# 05_POWER-SUPPLY.net
KiCad netlist of a schematic drawn in Altium Designer
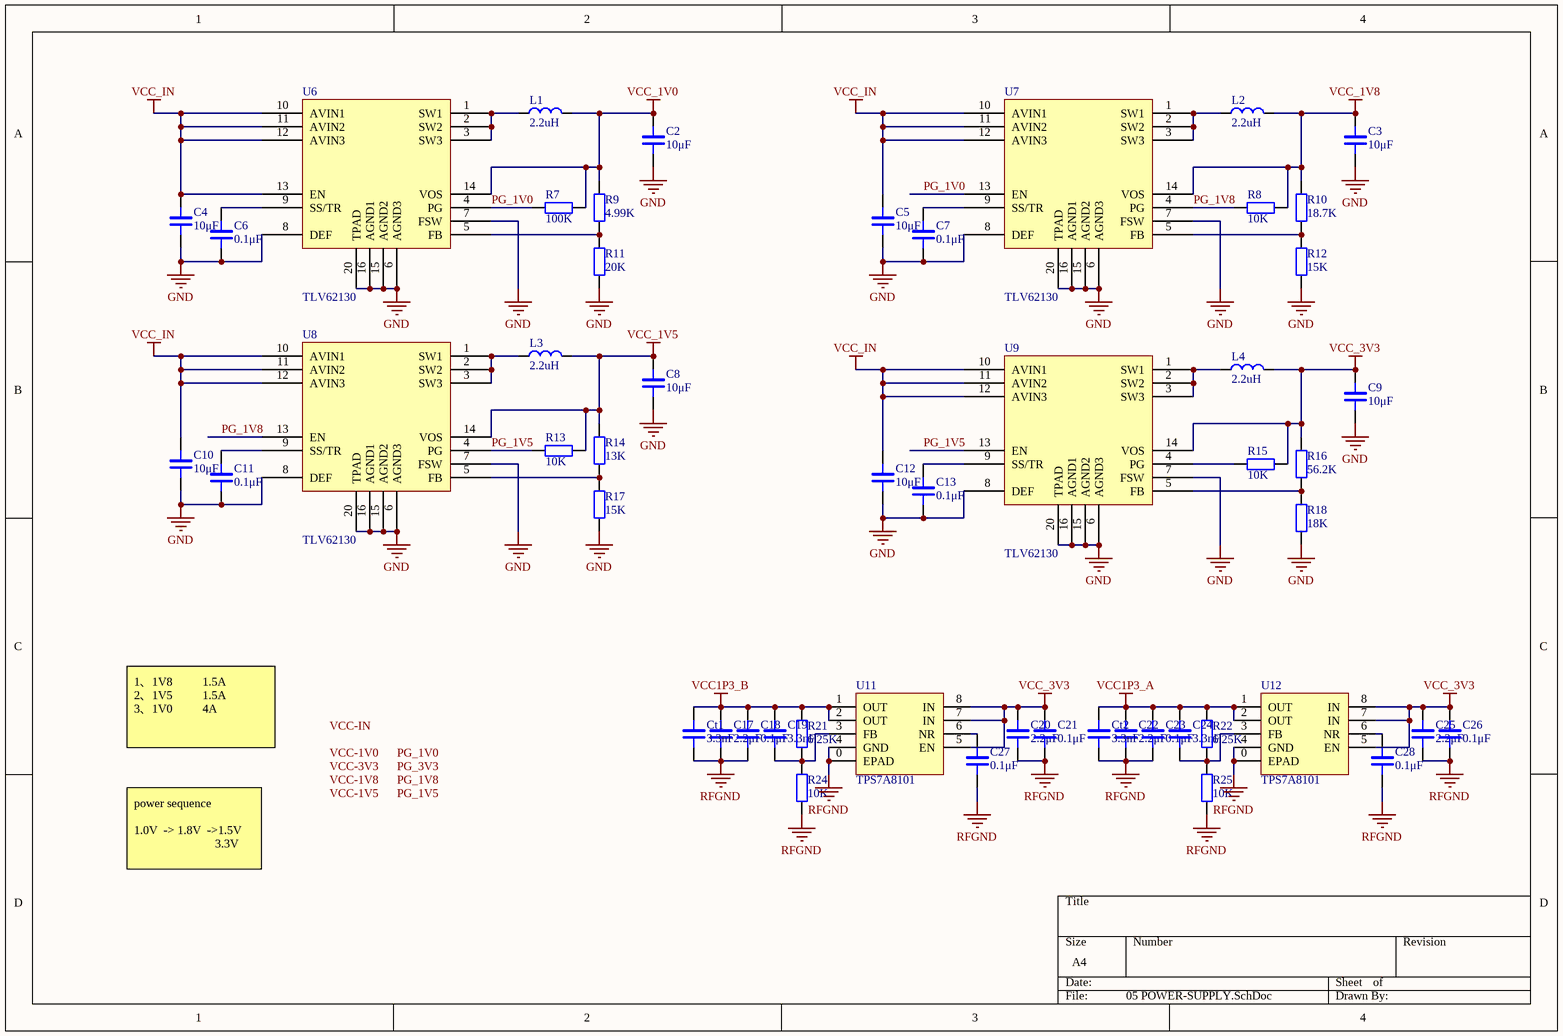
[diagram p0: 05 POWER-SUPPLY.SchDoc]

(export (version "E")
  (design (tool "Eeschema 10.0.6"))
  (components
    (comp (ref "C2")
      (value "10μF")
      (footprint "LC-0805_C")
      (description "Capacitor")
      (libsource (lib "NGFF_M_Key_xc7z010-clg400") (part "CAP_3"))
    )
    (comp (ref "C3")
      (value "10μF")
      (footprint "LC-0805_C")
      (description "Capacitor")
      (libsource (lib "NGFF_M_Key_xc7z010-clg400") (part "CAP_3"))
    )
    (comp (ref "C4")
      (value "10μF")
      (footprint "LC-0805_C")
      (description "Capacitor")
      (libsource (lib "NGFF_M_Key_xc7z010-clg400") (part "CAP_3"))
    )
    (comp (ref "C5")
      (value "10μF")
      (footprint "LC-0805_C")
      (description "Capacitor")
      (libsource (lib "NGFF_M_Key_xc7z010-clg400") (part "CAP_3"))
    )
    (comp (ref "C6")
      (value "0.1μF")
      (footprint "LC-0402_C")
      (description "Capacitor")
      (libsource (lib "NGFF_M_Key_xc7z010-clg400") (part "CAP_3"))
    )
    (comp (ref "C7")
      (value "0.1μF")
      (footprint "LC-0402_C")
      (description "Capacitor")
      (libsource (lib "NGFF_M_Key_xc7z010-clg400") (part "CAP_3"))
    )
    (comp (ref "C8")
      (value "10μF")
      (footprint "LC-0805_C")
      (description "Capacitor")
      (libsource (lib "NGFF_M_Key_xc7z010-clg400") (part "CAP_3"))
    )
    (comp (ref "C9")
      (value "10μF")
      (footprint "LC-0805_C")
      (description "Capacitor")
      (libsource (lib "NGFF_M_Key_xc7z010-clg400") (part "CAP_3"))
    )
    (comp (ref "C10")
      (value "10μF")
      (footprint "LC-0805_C")
      (description "Capacitor")
      (libsource (lib "NGFF_M_Key_xc7z010-clg400") (part "CAP_3"))
    )
    (comp (ref "C11")
      (value "0.1μF")
      (footprint "LC-0402_C")
      (description "Capacitor")
      (libsource (lib "NGFF_M_Key_xc7z010-clg400") (part "CAP_3"))
    )
    (comp (ref "C12")
      (value "10μF")
      (footprint "LC-0805_C")
      (description "Capacitor")
      (libsource (lib "NGFF_M_Key_xc7z010-clg400") (part "CAP_3"))
    )
    (comp (ref "C13")
      (value "0.1μF")
      (footprint "LC-0402_C")
      (description "Capacitor")
      (libsource (lib "NGFF_M_Key_xc7z010-clg400") (part "CAP_3"))
    )
    (comp (ref "C17")
      (value "2.2μF")
      (footprint "LC-0805_C")
      (description "Capacitor")
      (libsource (lib "NGFF_M_Key_xc7z010-clg400") (part "CAP_3"))
    )
    (comp (ref "C18")
      (value "0.1μF")
      (footprint "LC-0402_C")
      (description "Capacitor")
      (libsource (lib "NGFF_M_Key_xc7z010-clg400") (part "CAP_3"))
    )
    (comp (ref "C19")
      (value "3.3nF")
      (footprint "LC-0402_C")
      (description "Capacitor")
      (libsource (lib "NGFF_M_Key_xc7z010-clg400") (part "CAP_3"))
    )
    (comp (ref "C20")
      (value "2.2μF")
      (footprint "LC-0402_C")
      (description "Capacitor")
      (libsource (lib "NGFF_M_Key_xc7z010-clg400") (part "CAP_3"))
    )
    (comp (ref "C21")
      (value "0.1μF")
      (footprint "LC-0805_C")
      (description "Capacitor")
      (libsource (lib "NGFF_M_Key_xc7z010-clg400") (part "CAP_3"))
    )
    (comp (ref "C22")
      (value "2.2μF")
      (footprint "LC-0805_C")
      (description "Capacitor")
      (libsource (lib "NGFF_M_Key_xc7z010-clg400") (part "CAP_3"))
    )
    (comp (ref "C23")
      (value "0.1μF")
      (footprint "LC-0402_C")
      (description "Capacitor")
      (libsource (lib "NGFF_M_Key_xc7z010-clg400") (part "CAP_3"))
    )
    (comp (ref "C24")
      (value "3.3nF")
      (footprint "LC-0402_C")
      (description "Capacitor")
      (libsource (lib "NGFF_M_Key_xc7z010-clg400") (part "CAP_3"))
    )
    (comp (ref "C25")
      (value "2.2μF")
      (footprint "LC-0402_C")
      (description "Capacitor")
      (libsource (lib "NGFF_M_Key_xc7z010-clg400") (part "CAP_3"))
    )
    (comp (ref "C26")
      (value "0.1μF")
      (footprint "LC-0805_C")
      (description "Capacitor")
      (libsource (lib "NGFF_M_Key_xc7z010-clg400") (part "CAP_3"))
    )
    (comp (ref "C27")
      (value "0.1μF")
      (footprint "LC-0402_C")
      (description "Capacitor")
      (libsource (lib "NGFF_M_Key_xc7z010-clg400") (part "CAP_3"))
    )
    (comp (ref "C28")
      (value "0.1μF")
      (footprint "LC-0402_C")
      (description "Capacitor")
      (libsource (lib "NGFF_M_Key_xc7z010-clg400") (part "CAP_3"))
    )
    (comp (ref "Ct1")
      (value "3.3nF")
      (footprint "PCBComponent_1")
      (description "Capacitor")
      (libsource (lib "ZYNQ7010_AD9363") (part "CAP_3_3"))
    )
    (comp (ref "Ct2")
      (value "3.3nF")
      (footprint "PCBComponent_1")
      (description "Capacitor")
      (libsource (lib "ZYNQ7010_AD9363") (part "CAP_3_3"))
    )
    (comp (ref "L1")
      (value "2.2uH")
      (footprint "L1008")
      (description "Inductance")
      (libsource (lib "NGFF_M_Key_xc7z010-clg400") (part "INDUCTANCE_1"))
    )
    (comp (ref "L2")
      (value "2.2uH")
      (footprint "L1008")
      (description "Inductance")
      (libsource (lib "NGFF_M_Key_xc7z010-clg400") (part "INDUCTANCE_1"))
    )
    (comp (ref "L3")
      (value "2.2uH")
      (footprint "L1008")
      (description "Inductance")
      (libsource (lib "NGFF_M_Key_xc7z010-clg400") (part "INDUCTANCE_1"))
    )
    (comp (ref "L4")
      (value "2.2uH")
      (footprint "L1008")
      (description "Inductance")
      (libsource (lib "NGFF_M_Key_xc7z010-clg400") (part "INDUCTANCE_1"))
    )
    (comp (ref "R7")
      (value "100K")
      (footprint "LC-0402_R")
      (description "Resistor")
      (libsource (lib "") (part "RES_1"))
    )
    (comp (ref "R8")
      (value "10K")
      (footprint "LC-0402_R")
      (description "Resistor")
      (libsource (lib "") (part "RES_1"))
    )
    (comp (ref "R9")
      (value "4.99K")
      (footprint "LC-0402_R")
      (description "Resistor")
      (libsource (lib "NGFF_M_Key_xc7z010-clg400") (part "RES"))
    )
    (comp (ref "R10")
      (value "18.7K")
      (footprint "LC-0402_R")
      (description "Resistor")
      (libsource (lib "NGFF_M_Key_xc7z010-clg400") (part "RES"))
    )
    (comp (ref "R11")
      (value "20K")
      (footprint "LC-0402_R")
      (description "Resistor")
      (libsource (lib "NGFF_M_Key_xc7z010-clg400") (part "RES"))
    )
    (comp (ref "R12")
      (value "15K")
      (footprint "LC-0402_R")
      (description "Resistor")
      (libsource (lib "NGFF_M_Key_xc7z010-clg400") (part "RES"))
    )
    (comp (ref "R13")
      (value "10K")
      (footprint "LC-0402_R")
      (description "Resistor")
      (libsource (lib "") (part "RES_1"))
    )
    (comp (ref "R14")
      (value "13K")
      (footprint "LC-0402_R")
      (description "Resistor")
      (libsource (lib "NGFF_M_Key_xc7z010-clg400") (part "RES"))
    )
    (comp (ref "R15")
      (value "10K")
      (footprint "LC-0402_R")
      (description "Resistor")
      (libsource (lib "") (part "RES_1"))
    )
    (comp (ref "R16")
      (value "56.2K")
      (footprint "LC-0402_R")
      (description "Resistor")
      (libsource (lib "NGFF_M_Key_xc7z010-clg400") (part "RES"))
    )
    (comp (ref "R17")
      (value "15K")
      (footprint "LC-0402_R")
      (description "Resistor")
      (libsource (lib "NGFF_M_Key_xc7z010-clg400") (part "RES"))
    )
    (comp (ref "R18")
      (value "18K")
      (footprint "LC-0402_R")
      (description "Resistor")
      (libsource (lib "NGFF_M_Key_xc7z010-clg400") (part "RES"))
    )
    (comp (ref "R21")
      (value "6.25K")
      (footprint "LC-0402_R")
      (description "Resistor")
      (libsource (lib "NGFF_M_Key_xc7z010-clg400") (part "RES"))
    )
    (comp (ref "R22")
      (value "6.25K")
      (footprint "LC-0402_R")
      (description "Resistor")
      (libsource (lib "NGFF_M_Key_xc7z010-clg400") (part "RES"))
    )
    (comp (ref "R24")
      (value "10K")
      (footprint "LC-0402_R")
      (description "Resistor")
      (libsource (lib "NGFF_M_Key_xc7z010-clg400") (part "RES"))
    )
    (comp (ref "R25")
      (value "10K")
      (footprint "LC-0402_R")
      (description "Resistor")
      (libsource (lib "NGFF_M_Key_xc7z010-clg400") (part "RES"))
    )
    (comp (ref "U6")
      (value "TLV62130")
      (footprint "TLV62130RGT")
      (libsource (lib "PCB_Project") (part "TLV62130"))
    )
    (comp (ref "U7")
      (value "TLV62130")
      (footprint "TLV62130RGT")
      (libsource (lib "PCB_Project") (part "TLV62130"))
    )
    (comp (ref "U8")
      (value "TLV62130")
      (footprint "TLV62130RGT")
      (libsource (lib "PCB_Project") (part "TLV62130"))
    )
    (comp (ref "U9")
      (value "TLV62130")
      (footprint "TLV62130RGT")
      (libsource (lib "PCB_Project") (part "TLV62130"))
    )
    (comp (ref "U11")
      (value "TPS7A8101")
      (footprint "TPS7A8101")
      (libsource (lib "AD9363_ZYNQ_V2") (part "TPS7A8101"))
    )
    (comp (ref "U12")
      (value "TPS7A8101")
      (footprint "TPS7A8101")
      (libsource (lib "AD9363_ZYNQ_V2") (part "TPS7A8101"))
    )
  )
  (nets
    (net (code "1") (name "/PG_1V0") (class "Default")
      (node (ref "R7") (pin "2") (pinfunction "2_2") (pintype "passive"))
      (node (ref "U6") (pin "4") (pinfunction "PG_4") (pintype "passive"))
      (node (ref "U7") (pin "13") (pinfunction "EN_13") (pintype "passive"))
    )
    (net (code "2") (name "/PG_1V5") (class "Default")
      (node (ref "R13") (pin "2") (pinfunction "2_2") (pintype "passive"))
      (node (ref "U8") (pin "4") (pinfunction "PG_4") (pintype "passive"))
      (node (ref "U9") (pin "13") (pinfunction "EN_13") (pintype "passive"))
    )
    (net (code "3") (name "/PG_1V8") (class "Default")
      (node (ref "R8") (pin "2") (pinfunction "2_2") (pintype "passive"))
      (node (ref "U7") (pin "4") (pinfunction "PG_4") (pintype "passive"))
      (node (ref "U8") (pin "13") (pinfunction "EN_13") (pintype "passive"))
    )
    (net (code "10") (name "GND") (class "Default")
      (node (ref "C10") (pin "1") (pinfunction "1_1") (pintype "passive"))
      (node (ref "C11") (pin "1") (pinfunction "1_1") (pintype "passive"))
      (node (ref "C12") (pin "1") (pinfunction "1_1") (pintype "passive"))
      (node (ref "C13") (pin "1") (pinfunction "1_1") (pintype "passive"))
      (node (ref "C2") (pin "1") (pinfunction "1_1") (pintype "passive"))
      (node (ref "C3") (pin "1") (pinfunction "1_1") (pintype "passive"))
      (node (ref "C4") (pin "1") (pinfunction "1_1") (pintype "passive"))
      (node (ref "C5") (pin "1") (pinfunction "1_1") (pintype "passive"))
      (node (ref "C6") (pin "1") (pinfunction "1_1") (pintype "passive"))
      (node (ref "C7") (pin "1") (pinfunction "1_1") (pintype "passive"))
      (node (ref "C8") (pin "1") (pinfunction "1_1") (pintype "passive"))
      (node (ref "C9") (pin "1") (pinfunction "1_1") (pintype "passive"))
      (node (ref "R11") (pin "2") (pinfunction "2_2") (pintype "passive"))
      (node (ref "R12") (pin "2") (pinfunction "2_2") (pintype "passive"))
      (node (ref "R17") (pin "2") (pinfunction "2_2") (pintype "passive"))
      (node (ref "R18") (pin "2") (pinfunction "2_2") (pintype "passive"))
      (node (ref "U6") (pin "15") (pinfunction "AGND2_15") (pintype "passive"))
      (node (ref "U6") (pin "16") (pinfunction "AGND1_16") (pintype "passive"))
      (node (ref "U6") (pin "20") (pinfunction "TPAD_20") (pintype "passive"))
      (node (ref "U6") (pin "6") (pinfunction "AGND3_6") (pintype "passive"))
      (node (ref "U6") (pin "7") (pinfunction "FSW_7") (pintype "passive"))
      (node (ref "U6") (pin "8") (pinfunction "DEF_8") (pintype "passive"))
      (node (ref "U7") (pin "15") (pinfunction "AGND2_15") (pintype "passive"))
      (node (ref "U7") (pin "16") (pinfunction "AGND1_16") (pintype "passive"))
      (node (ref "U7") (pin "20") (pinfunction "TPAD_20") (pintype "passive"))
      (node (ref "U7") (pin "6") (pinfunction "AGND3_6") (pintype "passive"))
      (node (ref "U7") (pin "7") (pinfunction "FSW_7") (pintype "passive"))
      (node (ref "U7") (pin "8") (pinfunction "DEF_8") (pintype "passive"))
      (node (ref "U8") (pin "15") (pinfunction "AGND2_15") (pintype "passive"))
      (node (ref "U8") (pin "16") (pinfunction "AGND1_16") (pintype "passive"))
      (node (ref "U8") (pin "20") (pinfunction "TPAD_20") (pintype "passive"))
      (node (ref "U8") (pin "6") (pinfunction "AGND3_6") (pintype "passive"))
      (node (ref "U8") (pin "7") (pinfunction "FSW_7") (pintype "passive"))
      (node (ref "U8") (pin "8") (pinfunction "DEF_8") (pintype "passive"))
      (node (ref "U9") (pin "15") (pinfunction "AGND2_15") (pintype "passive"))
      (node (ref "U9") (pin "16") (pinfunction "AGND1_16") (pintype "passive"))
      (node (ref "U9") (pin "20") (pinfunction "TPAD_20") (pintype "passive"))
      (node (ref "U9") (pin "6") (pinfunction "AGND3_6") (pintype "passive"))
      (node (ref "U9") (pin "7") (pinfunction "FSW_7") (pintype "passive"))
      (node (ref "U9") (pin "8") (pinfunction "DEF_8") (pintype "passive"))
    )
    (net (code "11") (name "Net-(U6-FB)") (class "Default")
      (node (ref "R11") (pin "1") (pinfunction "1_1") (pintype "passive"))
      (node (ref "R9") (pin "2") (pinfunction "2_2") (pintype "passive"))
      (node (ref "U6") (pin "5") (pinfunction "FB_5") (pintype "passive"))
    )
    (net (code "12") (name "Net-(U6-SS{slash}TR)") (class "Default")
      (node (ref "C6") (pin "2") (pinfunction "2_2") (pintype "passive"))
      (node (ref "U6") (pin "9") (pinfunction "SS/TR_9") (pintype "passive"))
    )
    (net (code "13") (name "Net-(U6-SW1)") (class "Default")
      (node (ref "L1") (pin "1") (pinfunction "1_1") (pintype "passive"))
      (node (ref "U6") (pin "1") (pinfunction "SW1_1") (pintype "passive"))
      (node (ref "U6") (pin "2") (pinfunction "SW2_2") (pintype "passive"))
      (node (ref "U6") (pin "3") (pinfunction "SW3_3") (pintype "passive"))
    )
    (net (code "14") (name "Net-(U7-FB)") (class "Default")
      (node (ref "R10") (pin "2") (pinfunction "2_2") (pintype "passive"))
      (node (ref "R12") (pin "1") (pinfunction "1_1") (pintype "passive"))
      (node (ref "U7") (pin "5") (pinfunction "FB_5") (pintype "passive"))
    )
    (net (code "15") (name "Net-(U7-SS{slash}TR)") (class "Default")
      (node (ref "C7") (pin "2") (pinfunction "2_2") (pintype "passive"))
      (node (ref "U7") (pin "9") (pinfunction "SS/TR_9") (pintype "passive"))
    )
    (net (code "16") (name "Net-(U7-SW1)") (class "Default")
      (node (ref "L2") (pin "1") (pinfunction "1_1") (pintype "passive"))
      (node (ref "U7") (pin "1") (pinfunction "SW1_1") (pintype "passive"))
      (node (ref "U7") (pin "2") (pinfunction "SW2_2") (pintype "passive"))
      (node (ref "U7") (pin "3") (pinfunction "SW3_3") (pintype "passive"))
    )
    (net (code "17") (name "Net-(U8-FB)") (class "Default")
      (node (ref "R14") (pin "2") (pinfunction "2_2") (pintype "passive"))
      (node (ref "R17") (pin "1") (pinfunction "1_1") (pintype "passive"))
      (node (ref "U8") (pin "5") (pinfunction "FB_5") (pintype "passive"))
    )
    (net (code "18") (name "Net-(U8-SS{slash}TR)") (class "Default")
      (node (ref "C11") (pin "2") (pinfunction "2_2") (pintype "passive"))
      (node (ref "U8") (pin "9") (pinfunction "SS/TR_9") (pintype "passive"))
    )
    (net (code "19") (name "Net-(U8-SW1)") (class "Default")
      (node (ref "L3") (pin "1") (pinfunction "1_1") (pintype "passive"))
      (node (ref "U8") (pin "1") (pinfunction "SW1_1") (pintype "passive"))
      (node (ref "U8") (pin "2") (pinfunction "SW2_2") (pintype "passive"))
      (node (ref "U8") (pin "3") (pinfunction "SW3_3") (pintype "passive"))
    )
    (net (code "20") (name "Net-(U9-FB)") (class "Default")
      (node (ref "R16") (pin "2") (pinfunction "2_2") (pintype "passive"))
      (node (ref "R18") (pin "1") (pinfunction "1_1") (pintype "passive"))
      (node (ref "U9") (pin "5") (pinfunction "FB_5") (pintype "passive"))
    )
    (net (code "21") (name "Net-(U9-PG)") (class "Default")
      (node (ref "R15") (pin "2") (pinfunction "2_2") (pintype "passive"))
      (node (ref "U9") (pin "4") (pinfunction "PG_4") (pintype "passive"))
    )
    (net (code "22") (name "Net-(U9-SS{slash}TR)") (class "Default")
      (node (ref "C13") (pin "2") (pinfunction "2_2") (pintype "passive"))
      (node (ref "U9") (pin "9") (pinfunction "SS/TR_9") (pintype "passive"))
    )
    (net (code "23") (name "Net-(U9-SW1)") (class "Default")
      (node (ref "L4") (pin "1") (pinfunction "1_1") (pintype "passive"))
      (node (ref "U9") (pin "1") (pinfunction "SW1_1") (pintype "passive"))
      (node (ref "U9") (pin "2") (pinfunction "SW2_2") (pintype "passive"))
      (node (ref "U9") (pin "3") (pinfunction "SW3_3") (pintype "passive"))
    )
    (net (code "24") (name "Net-(U11-FB)") (class "Default")
      (node (ref "C19") (pin "1") (pinfunction "1_1") (pintype "passive"))
      (node (ref "R21") (pin "2") (pinfunction "2_2") (pintype "passive"))
      (node (ref "R24") (pin "1") (pinfunction "1_1") (pintype "passive"))
      (node (ref "U11") (pin "3") (pinfunction "FB_3") (pintype "passive"))
    )
    (net (code "25") (name "Net-(U11-NR)") (class "Default")
      (node (ref "C27") (pin "2") (pinfunction "2_2") (pintype "passive"))
      (node (ref "U11") (pin "6") (pinfunction "NR_6") (pintype "passive"))
    )
    (net (code "26") (name "Net-(U12-FB)") (class "Default")
      (node (ref "C24") (pin "1") (pinfunction "1_1") (pintype "passive"))
      (node (ref "R22") (pin "2") (pinfunction "2_2") (pintype "passive"))
      (node (ref "R25") (pin "1") (pinfunction "1_1") (pintype "passive"))
      (node (ref "U12") (pin "3") (pinfunction "FB_3") (pintype "passive"))
    )
    (net (code "27") (name "Net-(U12-NR)") (class "Default")
      (node (ref "C28") (pin "2") (pinfunction "2_2") (pintype "passive"))
      (node (ref "U12") (pin "6") (pinfunction "NR_6") (pintype "passive"))
    )
    (net (code "28") (name "RFGND") (class "Default")
      (node (ref "C17") (pin "1") (pinfunction "1_1") (pintype "passive"))
      (node (ref "C18") (pin "1") (pinfunction "1_1") (pintype "passive"))
      (node (ref "C20") (pin "1") (pinfunction "1_1") (pintype "passive"))
      (node (ref "C21") (pin "1") (pinfunction "1_1") (pintype "passive"))
      (node (ref "C22") (pin "1") (pinfunction "1_1") (pintype "passive"))
      (node (ref "C23") (pin "1") (pinfunction "1_1") (pintype "passive"))
      (node (ref "C25") (pin "1") (pinfunction "1_1") (pintype "passive"))
      (node (ref "C26") (pin "1") (pinfunction "1_1") (pintype "passive"))
      (node (ref "C27") (pin "1") (pinfunction "1_1") (pintype "passive"))
      (node (ref "C28") (pin "1") (pinfunction "1_1") (pintype "passive"))
      (node (ref "Ct1") (pin "2") (pinfunction "2_2") (pintype "passive"))
      (node (ref "Ct2") (pin "2") (pinfunction "2_2") (pintype "passive"))
      (node (ref "R24") (pin "2") (pinfunction "2_2") (pintype "passive"))
      (node (ref "R25") (pin "2") (pinfunction "2_2") (pintype "passive"))
      (node (ref "U11") (pin "0") (pinfunction "EPAD_0") (pintype "passive"))
      (node (ref "U11") (pin "4") (pinfunction "GND_4") (pintype "passive"))
      (node (ref "U12") (pin "0") (pinfunction "EPAD_0") (pintype "passive"))
      (node (ref "U12") (pin "4") (pinfunction "GND_4") (pintype "passive"))
    )
    (net (code "29") (name "VCC1P3_A") (class "Default")
      (node (ref "C22") (pin "2") (pinfunction "2_2") (pintype "passive"))
      (node (ref "C23") (pin "2") (pinfunction "2_2") (pintype "passive"))
      (node (ref "C24") (pin "2") (pinfunction "2_2") (pintype "passive"))
      (node (ref "Ct2") (pin "1") (pinfunction "1_1") (pintype "passive"))
      (node (ref "R22") (pin "1") (pinfunction "1_1") (pintype "passive"))
      (node (ref "U12") (pin "1") (pinfunction "OUT_1") (pintype "passive"))
      (node (ref "U12") (pin "2") (pinfunction "OUT_2") (pintype "passive"))
    )
    (net (code "30") (name "VCC1P3_B") (class "Default")
      (node (ref "C17") (pin "2") (pinfunction "2_2") (pintype "passive"))
      (node (ref "C18") (pin "2") (pinfunction "2_2") (pintype "passive"))
      (node (ref "C19") (pin "2") (pinfunction "2_2") (pintype "passive"))
      (node (ref "Ct1") (pin "1") (pinfunction "1_1") (pintype "passive"))
      (node (ref "R21") (pin "1") (pinfunction "1_1") (pintype "passive"))
      (node (ref "U11") (pin "1") (pinfunction "OUT_1") (pintype "passive"))
      (node (ref "U11") (pin "2") (pinfunction "OUT_2") (pintype "passive"))
    )
    (net (code "31") (name "VCC_1V0") (class "Default")
      (node (ref "C2") (pin "2") (pinfunction "2_2") (pintype "passive"))
      (node (ref "L1") (pin "2") (pinfunction "2_2") (pintype "passive"))
      (node (ref "R7") (pin "1") (pinfunction "1_1") (pintype "passive"))
      (node (ref "R9") (pin "1") (pinfunction "1_1") (pintype "passive"))
      (node (ref "U6") (pin "14") (pinfunction "VOS_14") (pintype "passive"))
    )
    (net (code "32") (name "VCC_1V5") (class "Default")
      (node (ref "C8") (pin "2") (pinfunction "2_2") (pintype "passive"))
      (node (ref "L3") (pin "2") (pinfunction "2_2") (pintype "passive"))
      (node (ref "R13") (pin "1") (pinfunction "1_1") (pintype "passive"))
      (node (ref "R14") (pin "1") (pinfunction "1_1") (pintype "passive"))
      (node (ref "U8") (pin "14") (pinfunction "VOS_14") (pintype "passive"))
    )
    (net (code "33") (name "VCC_1V8") (class "Default")
      (node (ref "C3") (pin "2") (pinfunction "2_2") (pintype "passive"))
      (node (ref "L2") (pin "2") (pinfunction "2_2") (pintype "passive"))
      (node (ref "R10") (pin "1") (pinfunction "1_1") (pintype "passive"))
      (node (ref "R8") (pin "1") (pinfunction "1_1") (pintype "passive"))
      (node (ref "U7") (pin "14") (pinfunction "VOS_14") (pintype "passive"))
    )
    (net (code "34") (name "VCC_3V3") (class "Default")
      (node (ref "C20") (pin "2") (pinfunction "2_2") (pintype "passive"))
      (node (ref "C21") (pin "2") (pinfunction "2_2") (pintype "passive"))
      (node (ref "C25") (pin "2") (pinfunction "2_2") (pintype "passive"))
      (node (ref "C26") (pin "2") (pinfunction "2_2") (pintype "passive"))
      (node (ref "C9") (pin "2") (pinfunction "2_2") (pintype "passive"))
      (node (ref "L4") (pin "2") (pinfunction "2_2") (pintype "passive"))
      (node (ref "R15") (pin "1") (pinfunction "1_1") (pintype "passive"))
      (node (ref "R16") (pin "1") (pinfunction "1_1") (pintype "passive"))
      (node (ref "U11") (pin "5") (pinfunction "EN_5") (pintype "passive"))
      (node (ref "U11") (pin "7") (pinfunction "IN_7") (pintype "passive"))
      (node (ref "U11") (pin "8") (pinfunction "IN_8") (pintype "passive"))
      (node (ref "U12") (pin "5") (pinfunction "EN_5") (pintype "passive"))
      (node (ref "U12") (pin "7") (pinfunction "IN_7") (pintype "passive"))
      (node (ref "U12") (pin "8") (pinfunction "IN_8") (pintype "passive"))
      (node (ref "U9") (pin "14") (pinfunction "VOS_14") (pintype "passive"))
    )
    (net (code "35") (name "VCC_IN") (class "Default")
      (node (ref "C10") (pin "2") (pinfunction "2_2") (pintype "passive"))
      (node (ref "C12") (pin "2") (pinfunction "2_2") (pintype "passive"))
      (node (ref "C4") (pin "2") (pinfunction "2_2") (pintype "passive"))
      (node (ref "C5") (pin "2") (pinfunction "2_2") (pintype "passive"))
      (node (ref "U6") (pin "10") (pinfunction "AVIN1_10") (pintype "passive"))
      (node (ref "U6") (pin "11") (pinfunction "AVIN2_11") (pintype "passive"))
      (node (ref "U6") (pin "12") (pinfunction "AVIN3_12") (pintype "passive"))
      (node (ref "U6") (pin "13") (pinfunction "EN_13") (pintype "passive"))
      (node (ref "U7") (pin "10") (pinfunction "AVIN1_10") (pintype "passive"))
      (node (ref "U7") (pin "11") (pinfunction "AVIN2_11") (pintype "passive"))
      (node (ref "U7") (pin "12") (pinfunction "AVIN3_12") (pintype "passive"))
      (node (ref "U8") (pin "10") (pinfunction "AVIN1_10") (pintype "passive"))
      (node (ref "U8") (pin "11") (pinfunction "AVIN2_11") (pintype "passive"))
      (node (ref "U8") (pin "12") (pinfunction "AVIN3_12") (pintype "passive"))
      (node (ref "U9") (pin "10") (pinfunction "AVIN1_10") (pintype "passive"))
      (node (ref "U9") (pin "11") (pinfunction "AVIN2_11") (pintype "passive"))
      (node (ref "U9") (pin "12") (pinfunction "AVIN3_12") (pintype "passive"))
    )
  )
)
